# InterfaceUSB6TVSBoard.net
KiCad netlist of a schematic drawn in EAGLE
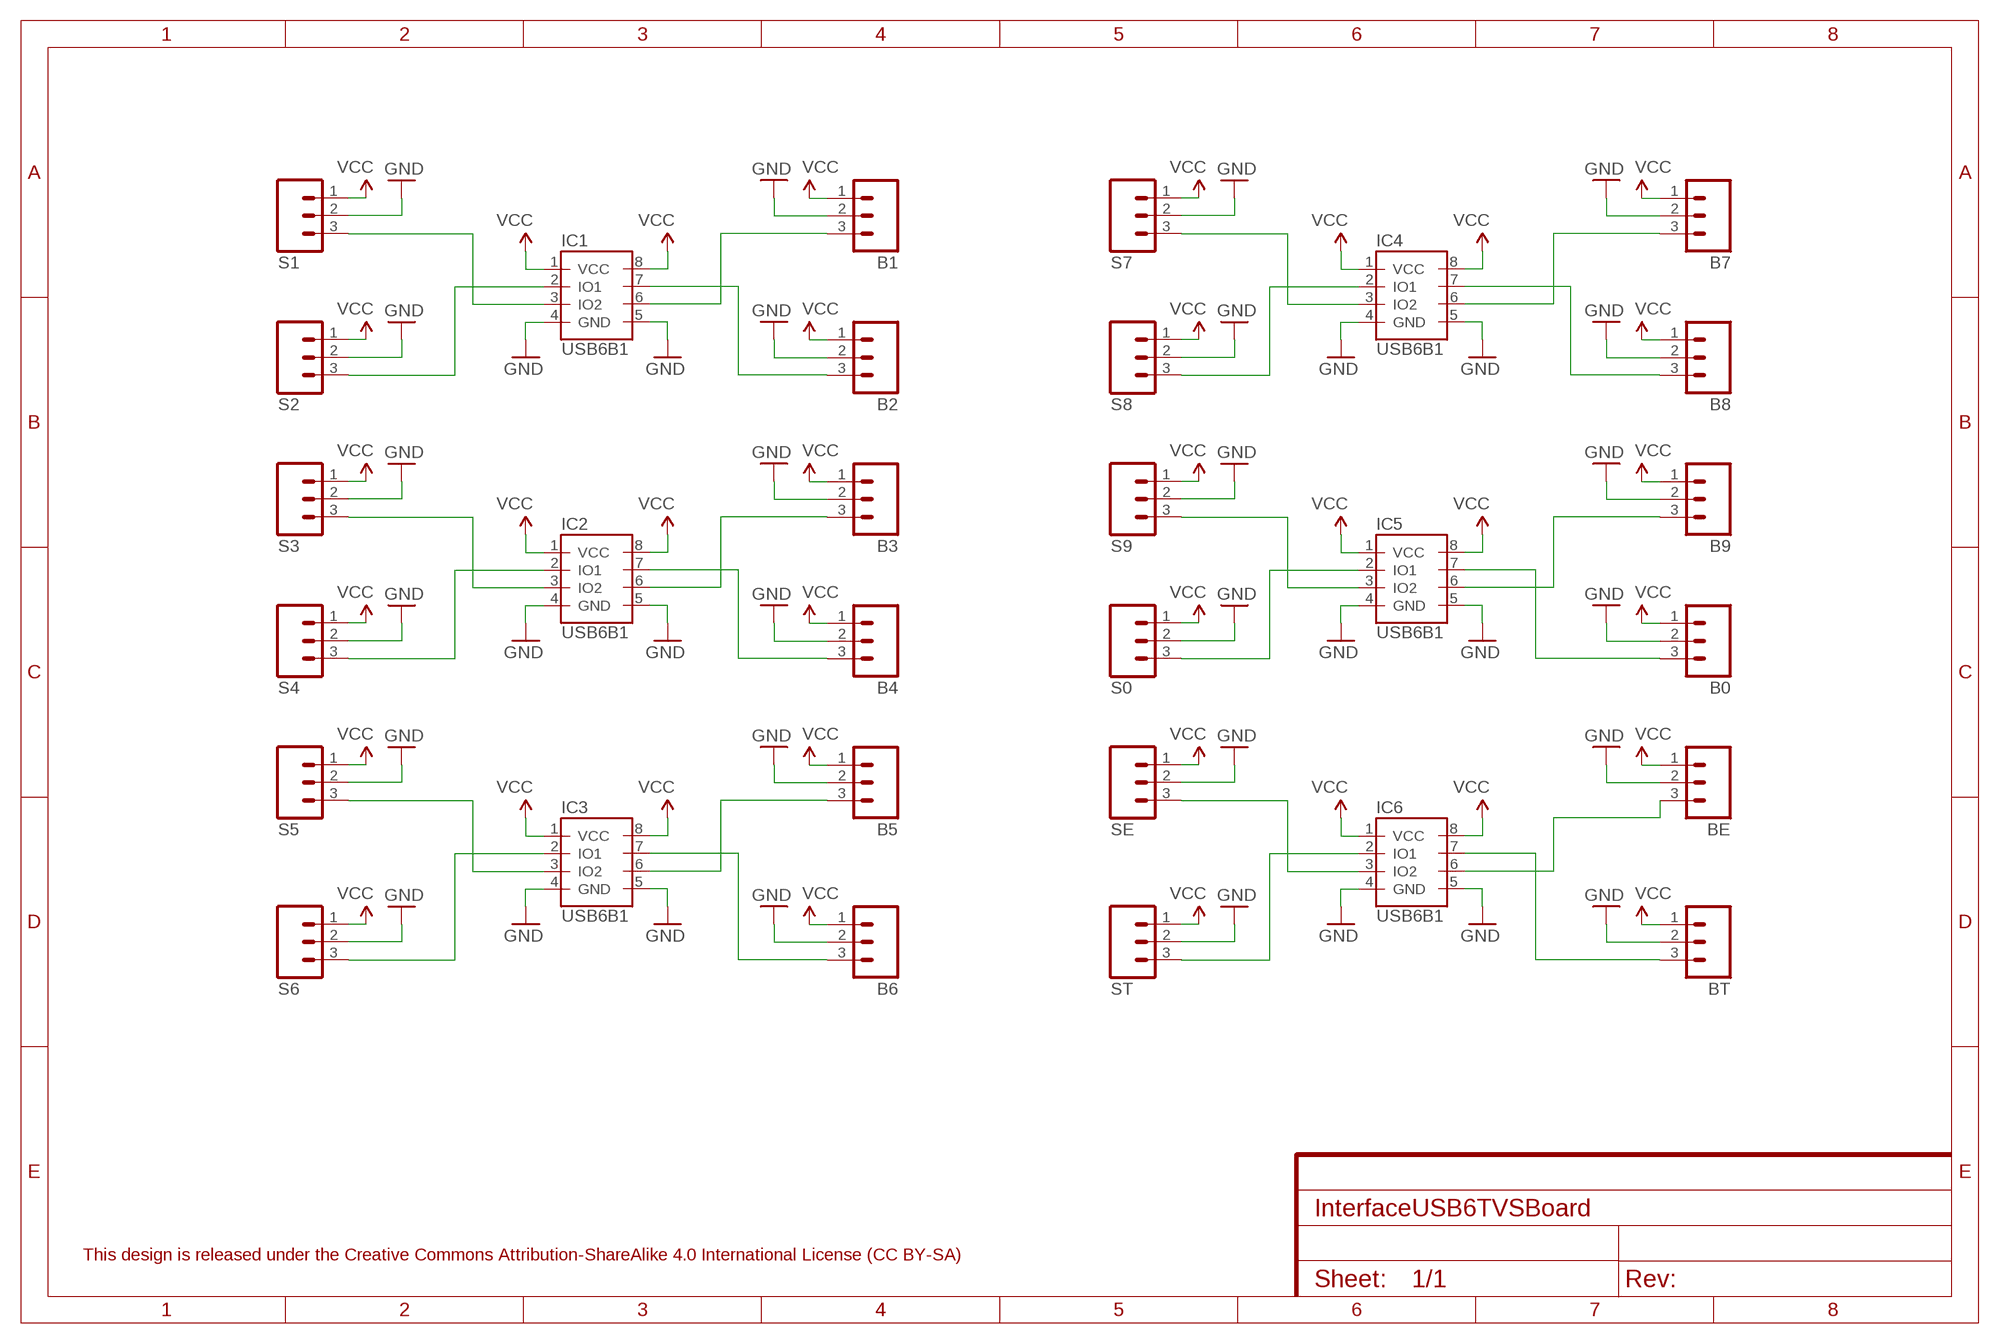
[diagram p0: schematic, sheet 1]

(export (version "E")
  (design (tool "Eeschema 10.0.6"))
  (components
    (comp (ref "B0")
      (value "M03PTH")
      (footprint "eagle-import:1X03")
      (libsource (lib "eagle-import") (part "M03PTH"))
    )
    (comp (ref "B1")
      (value "M03PTH")
      (footprint "eagle-import:1X03")
      (libsource (lib "eagle-import") (part "M03PTH"))
    )
    (comp (ref "B2")
      (value "M03PTH")
      (footprint "eagle-import:1X03")
      (libsource (lib "eagle-import") (part "M03PTH"))
    )
    (comp (ref "B3")
      (value "M03PTH")
      (footprint "eagle-import:1X03")
      (libsource (lib "eagle-import") (part "M03PTH"))
    )
    (comp (ref "B4")
      (value "M03PTH")
      (footprint "eagle-import:1X03")
      (libsource (lib "eagle-import") (part "M03PTH"))
    )
    (comp (ref "B5")
      (value "M03PTH")
      (footprint "eagle-import:1X03")
      (libsource (lib "eagle-import") (part "M03PTH"))
    )
    (comp (ref "B6")
      (value "M03PTH")
      (footprint "eagle-import:1X03")
      (libsource (lib "eagle-import") (part "M03PTH"))
    )
    (comp (ref "B7")
      (value "M03PTH")
      (footprint "eagle-import:1X03")
      (libsource (lib "eagle-import") (part "M03PTH"))
    )
    (comp (ref "B8")
      (value "M03PTH")
      (footprint "eagle-import:1X03")
      (libsource (lib "eagle-import") (part "M03PTH"))
    )
    (comp (ref "B9")
      (value "M03PTH")
      (footprint "eagle-import:1X03")
      (libsource (lib "eagle-import") (part "M03PTH"))
    )
    (comp (ref "BE")
      (value "M03PTH")
      (footprint "eagle-import:1X03")
      (libsource (lib "eagle-import") (part "M03PTH"))
    )
    (comp (ref "BT")
      (value "M03PTH")
      (footprint "eagle-import:1X03")
      (libsource (lib "eagle-import") (part "M03PTH"))
    )
    (comp (ref "IC1")
      (value "USB6B1")
      (footprint "eagle-import:SO08")
      (libsource (lib "eagle-import") (part "USB6B1"))
    )
    (comp (ref "IC2")
      (value "USB6B1")
      (footprint "eagle-import:SO08")
      (libsource (lib "eagle-import") (part "USB6B1"))
    )
    (comp (ref "IC3")
      (value "USB6B1")
      (footprint "eagle-import:SO08")
      (libsource (lib "eagle-import") (part "USB6B1"))
    )
    (comp (ref "IC4")
      (value "USB6B1")
      (footprint "eagle-import:SO08")
      (libsource (lib "eagle-import") (part "USB6B1"))
    )
    (comp (ref "IC5")
      (value "USB6B1")
      (footprint "eagle-import:SO08")
      (libsource (lib "eagle-import") (part "USB6B1"))
    )
    (comp (ref "IC6")
      (value "USB6B1")
      (footprint "eagle-import:SO08")
      (libsource (lib "eagle-import") (part "USB6B1"))
    )
    (comp (ref "S0")
      (value "M03PTH")
      (footprint "eagle-import:1X03")
      (libsource (lib "eagle-import") (part "M03PTH"))
    )
    (comp (ref "S1")
      (value "M03PTH")
      (footprint "eagle-import:1X03")
      (libsource (lib "eagle-import") (part "M03PTH"))
    )
    (comp (ref "S2")
      (value "M03PTH")
      (footprint "eagle-import:1X03")
      (libsource (lib "eagle-import") (part "M03PTH"))
    )
    (comp (ref "S3")
      (value "M03PTH")
      (footprint "eagle-import:1X03")
      (libsource (lib "eagle-import") (part "M03PTH"))
    )
    (comp (ref "S4")
      (value "M03PTH")
      (footprint "eagle-import:1X03")
      (libsource (lib "eagle-import") (part "M03PTH"))
    )
    (comp (ref "S5")
      (value "M03PTH")
      (footprint "eagle-import:1X03")
      (libsource (lib "eagle-import") (part "M03PTH"))
    )
    (comp (ref "S6")
      (value "M03PTH")
      (footprint "eagle-import:1X03")
      (libsource (lib "eagle-import") (part "M03PTH"))
    )
    (comp (ref "S7")
      (value "M03PTH")
      (footprint "eagle-import:1X03")
      (libsource (lib "eagle-import") (part "M03PTH"))
    )
    (comp (ref "S8")
      (value "M03PTH")
      (footprint "eagle-import:1X03")
      (libsource (lib "eagle-import") (part "M03PTH"))
    )
    (comp (ref "S9")
      (value "M03PTH")
      (footprint "eagle-import:1X03")
      (libsource (lib "eagle-import") (part "M03PTH"))
    )
    (comp (ref "SE")
      (value "M03PTH")
      (footprint "eagle-import:1X03")
      (libsource (lib "eagle-import") (part "M03PTH"))
    )
    (comp (ref "ST")
      (value "M03PTH")
      (footprint "eagle-import:1X03")
      (libsource (lib "eagle-import") (part "M03PTH"))
    )
  )
  (nets
    (net (code "1") (name "GND") (class "Default")
      (node (ref "B0") (pin "2") (pinfunction "2_2") (pintype "passive"))
      (node (ref "B1") (pin "2") (pinfunction "2_2") (pintype "passive"))
      (node (ref "B2") (pin "2") (pinfunction "2_2") (pintype "passive"))
      (node (ref "B3") (pin "2") (pinfunction "2_2") (pintype "passive"))
      (node (ref "B4") (pin "2") (pinfunction "2_2") (pintype "passive"))
      (node (ref "B5") (pin "2") (pinfunction "2_2") (pintype "passive"))
      (node (ref "B6") (pin "2") (pinfunction "2_2") (pintype "passive"))
      (node (ref "B7") (pin "2") (pinfunction "2_2") (pintype "passive"))
      (node (ref "B8") (pin "2") (pinfunction "2_2") (pintype "passive"))
      (node (ref "B9") (pin "2") (pinfunction "2_2") (pintype "passive"))
      (node (ref "BE") (pin "2") (pinfunction "2_2") (pintype "passive"))
      (node (ref "BT") (pin "2") (pinfunction "2_2") (pintype "passive"))
      (node (ref "IC1") (pin "4") (pinfunction "GND_4") (pintype "power_in"))
      (node (ref "IC1") (pin "5") (pinfunction "GND_5") (pintype "power_in"))
      (node (ref "IC2") (pin "4") (pinfunction "GND_4") (pintype "power_in"))
      (node (ref "IC2") (pin "5") (pinfunction "GND_5") (pintype "power_in"))
      (node (ref "IC3") (pin "4") (pinfunction "GND_4") (pintype "power_in"))
      (node (ref "IC3") (pin "5") (pinfunction "GND_5") (pintype "power_in"))
      (node (ref "IC4") (pin "4") (pinfunction "GND_4") (pintype "power_in"))
      (node (ref "IC4") (pin "5") (pinfunction "GND_5") (pintype "power_in"))
      (node (ref "IC5") (pin "4") (pinfunction "GND_4") (pintype "power_in"))
      (node (ref "IC5") (pin "5") (pinfunction "GND_5") (pintype "power_in"))
      (node (ref "IC6") (pin "4") (pinfunction "GND_4") (pintype "power_in"))
      (node (ref "IC6") (pin "5") (pinfunction "GND_5") (pintype "power_in"))
      (node (ref "S0") (pin "2") (pinfunction "2_2") (pintype "passive"))
      (node (ref "S1") (pin "2") (pinfunction "2_2") (pintype "passive"))
      (node (ref "S2") (pin "2") (pinfunction "2_2") (pintype "passive"))
      (node (ref "S3") (pin "2") (pinfunction "2_2") (pintype "passive"))
      (node (ref "S4") (pin "2") (pinfunction "2_2") (pintype "passive"))
      (node (ref "S5") (pin "2") (pinfunction "2_2") (pintype "passive"))
      (node (ref "S6") (pin "2") (pinfunction "2_2") (pintype "passive"))
      (node (ref "S7") (pin "2") (pinfunction "2_2") (pintype "passive"))
      (node (ref "S8") (pin "2") (pinfunction "2_2") (pintype "passive"))
      (node (ref "S9") (pin "2") (pinfunction "2_2") (pintype "passive"))
      (node (ref "SE") (pin "2") (pinfunction "2_2") (pintype "passive"))
      (node (ref "ST") (pin "2") (pinfunction "2_2") (pintype "passive"))
    )
    (net (code "2") (name "Net-(B0-Pad3)") (class "Default")
      (node (ref "B0") (pin "3") (pinfunction "3_3") (pintype "passive"))
      (node (ref "IC5") (pin "7") (pinfunction "IO1_7") (pintype "bidirectional"))
    )
    (net (code "3") (name "Net-(B1-Pad3)") (class "Default")
      (node (ref "B1") (pin "3") (pinfunction "3_3") (pintype "passive"))
      (node (ref "IC1") (pin "6") (pinfunction "IO2_6") (pintype "bidirectional"))
    )
    (net (code "4") (name "Net-(B2-Pad3)") (class "Default")
      (node (ref "B2") (pin "3") (pinfunction "3_3") (pintype "passive"))
      (node (ref "IC1") (pin "7") (pinfunction "IO1_7") (pintype "bidirectional"))
    )
    (net (code "5") (name "Net-(B3-Pad3)") (class "Default")
      (node (ref "B3") (pin "3") (pinfunction "3_3") (pintype "passive"))
      (node (ref "IC2") (pin "6") (pinfunction "IO2_6") (pintype "bidirectional"))
    )
    (net (code "6") (name "Net-(B4-Pad3)") (class "Default")
      (node (ref "B4") (pin "3") (pinfunction "3_3") (pintype "passive"))
      (node (ref "IC2") (pin "7") (pinfunction "IO1_7") (pintype "bidirectional"))
    )
    (net (code "7") (name "Net-(B5-Pad3)") (class "Default")
      (node (ref "B5") (pin "3") (pinfunction "3_3") (pintype "passive"))
      (node (ref "IC3") (pin "6") (pinfunction "IO2_6") (pintype "bidirectional"))
    )
    (net (code "8") (name "Net-(B6-Pad3)") (class "Default")
      (node (ref "B6") (pin "3") (pinfunction "3_3") (pintype "passive"))
      (node (ref "IC3") (pin "7") (pinfunction "IO1_7") (pintype "bidirectional"))
    )
    (net (code "9") (name "Net-(B7-Pad3)") (class "Default")
      (node (ref "B7") (pin "3") (pinfunction "3_3") (pintype "passive"))
      (node (ref "IC4") (pin "6") (pinfunction "IO2_6") (pintype "bidirectional"))
    )
    (net (code "10") (name "Net-(B8-Pad3)") (class "Default")
      (node (ref "B8") (pin "3") (pinfunction "3_3") (pintype "passive"))
      (node (ref "IC4") (pin "7") (pinfunction "IO1_7") (pintype "bidirectional"))
    )
    (net (code "11") (name "Net-(B9-Pad3)") (class "Default")
      (node (ref "B9") (pin "3") (pinfunction "3_3") (pintype "passive"))
      (node (ref "IC5") (pin "6") (pinfunction "IO2_6") (pintype "bidirectional"))
    )
    (net (code "12") (name "Net-(BE-Pad3)") (class "Default")
      (node (ref "BE") (pin "3") (pinfunction "3_3") (pintype "passive"))
      (node (ref "IC6") (pin "6") (pinfunction "IO2_6") (pintype "bidirectional"))
    )
    (net (code "13") (name "Net-(BT-Pad3)") (class "Default")
      (node (ref "BT") (pin "3") (pinfunction "3_3") (pintype "passive"))
      (node (ref "IC6") (pin "7") (pinfunction "IO1_7") (pintype "bidirectional"))
    )
    (net (code "14") (name "Net-(IC1-IO1-Pad2)") (class "Default")
      (node (ref "IC1") (pin "2") (pinfunction "IO1_2") (pintype "bidirectional"))
      (node (ref "S2") (pin "3") (pinfunction "3_3") (pintype "passive"))
    )
    (net (code "15") (name "Net-(IC1-IO2-Pad3)") (class "Default")
      (node (ref "IC1") (pin "3") (pinfunction "IO2_3") (pintype "bidirectional"))
      (node (ref "S1") (pin "3") (pinfunction "3_3") (pintype "passive"))
    )
    (net (code "16") (name "Net-(IC2-IO1-Pad2)") (class "Default")
      (node (ref "IC2") (pin "2") (pinfunction "IO1_2") (pintype "bidirectional"))
      (node (ref "S4") (pin "3") (pinfunction "3_3") (pintype "passive"))
    )
    (net (code "17") (name "Net-(IC2-IO2-Pad3)") (class "Default")
      (node (ref "IC2") (pin "3") (pinfunction "IO2_3") (pintype "bidirectional"))
      (node (ref "S3") (pin "3") (pinfunction "3_3") (pintype "passive"))
    )
    (net (code "18") (name "Net-(IC3-IO1-Pad2)") (class "Default")
      (node (ref "IC3") (pin "2") (pinfunction "IO1_2") (pintype "bidirectional"))
      (node (ref "S6") (pin "3") (pinfunction "3_3") (pintype "passive"))
    )
    (net (code "19") (name "Net-(IC3-IO2-Pad3)") (class "Default")
      (node (ref "IC3") (pin "3") (pinfunction "IO2_3") (pintype "bidirectional"))
      (node (ref "S5") (pin "3") (pinfunction "3_3") (pintype "passive"))
    )
    (net (code "20") (name "Net-(IC4-IO1-Pad2)") (class "Default")
      (node (ref "IC4") (pin "2") (pinfunction "IO1_2") (pintype "bidirectional"))
      (node (ref "S8") (pin "3") (pinfunction "3_3") (pintype "passive"))
    )
    (net (code "21") (name "Net-(IC4-IO2-Pad3)") (class "Default")
      (node (ref "IC4") (pin "3") (pinfunction "IO2_3") (pintype "bidirectional"))
      (node (ref "S7") (pin "3") (pinfunction "3_3") (pintype "passive"))
    )
    (net (code "22") (name "Net-(IC5-IO1-Pad2)") (class "Default")
      (node (ref "IC5") (pin "2") (pinfunction "IO1_2") (pintype "bidirectional"))
      (node (ref "S0") (pin "3") (pinfunction "3_3") (pintype "passive"))
    )
    (net (code "23") (name "Net-(IC5-IO2-Pad3)") (class "Default")
      (node (ref "IC5") (pin "3") (pinfunction "IO2_3") (pintype "bidirectional"))
      (node (ref "S9") (pin "3") (pinfunction "3_3") (pintype "passive"))
    )
    (net (code "24") (name "Net-(IC6-IO1-Pad2)") (class "Default")
      (node (ref "IC6") (pin "2") (pinfunction "IO1_2") (pintype "bidirectional"))
      (node (ref "ST") (pin "3") (pinfunction "3_3") (pintype "passive"))
    )
    (net (code "25") (name "Net-(IC6-IO2-Pad3)") (class "Default")
      (node (ref "IC6") (pin "3") (pinfunction "IO2_3") (pintype "bidirectional"))
      (node (ref "SE") (pin "3") (pinfunction "3_3") (pintype "passive"))
    )
    (net (code "26") (name "VCC") (class "Default")
      (node (ref "B0") (pin "1") (pinfunction "1_1") (pintype "passive"))
      (node (ref "B1") (pin "1") (pinfunction "1_1") (pintype "passive"))
      (node (ref "B2") (pin "1") (pinfunction "1_1") (pintype "passive"))
      (node (ref "B3") (pin "1") (pinfunction "1_1") (pintype "passive"))
      (node (ref "B4") (pin "1") (pinfunction "1_1") (pintype "passive"))
      (node (ref "B5") (pin "1") (pinfunction "1_1") (pintype "passive"))
      (node (ref "B6") (pin "1") (pinfunction "1_1") (pintype "passive"))
      (node (ref "B7") (pin "1") (pinfunction "1_1") (pintype "passive"))
      (node (ref "B8") (pin "1") (pinfunction "1_1") (pintype "passive"))
      (node (ref "B9") (pin "1") (pinfunction "1_1") (pintype "passive"))
      (node (ref "BE") (pin "1") (pinfunction "1_1") (pintype "passive"))
      (node (ref "BT") (pin "1") (pinfunction "1_1") (pintype "passive"))
      (node (ref "IC1") (pin "1") (pinfunction "VCC_1") (pintype "power_in"))
      (node (ref "IC1") (pin "8") (pinfunction "VCC_8") (pintype "power_in"))
      (node (ref "IC2") (pin "1") (pinfunction "VCC_1") (pintype "power_in"))
      (node (ref "IC2") (pin "8") (pinfunction "VCC_8") (pintype "power_in"))
      (node (ref "IC3") (pin "1") (pinfunction "VCC_1") (pintype "power_in"))
      (node (ref "IC3") (pin "8") (pinfunction "VCC_8") (pintype "power_in"))
      (node (ref "IC4") (pin "1") (pinfunction "VCC_1") (pintype "power_in"))
      (node (ref "IC4") (pin "8") (pinfunction "VCC_8") (pintype "power_in"))
      (node (ref "IC5") (pin "1") (pinfunction "VCC_1") (pintype "power_in"))
      (node (ref "IC5") (pin "8") (pinfunction "VCC_8") (pintype "power_in"))
      (node (ref "IC6") (pin "1") (pinfunction "VCC_1") (pintype "power_in"))
      (node (ref "IC6") (pin "8") (pinfunction "VCC_8") (pintype "power_in"))
      (node (ref "S0") (pin "1") (pinfunction "1_1") (pintype "passive"))
      (node (ref "S1") (pin "1") (pinfunction "1_1") (pintype "passive"))
      (node (ref "S2") (pin "1") (pinfunction "1_1") (pintype "passive"))
      (node (ref "S3") (pin "1") (pinfunction "1_1") (pintype "passive"))
      (node (ref "S4") (pin "1") (pinfunction "1_1") (pintype "passive"))
      (node (ref "S5") (pin "1") (pinfunction "1_1") (pintype "passive"))
      (node (ref "S6") (pin "1") (pinfunction "1_1") (pintype "passive"))
      (node (ref "S7") (pin "1") (pinfunction "1_1") (pintype "passive"))
      (node (ref "S8") (pin "1") (pinfunction "1_1") (pintype "passive"))
      (node (ref "S9") (pin "1") (pinfunction "1_1") (pintype "passive"))
      (node (ref "SE") (pin "1") (pinfunction "1_1") (pintype "passive"))
      (node (ref "ST") (pin "1") (pinfunction "1_1") (pintype "passive"))
    )
  )
)
